# Power.net
KiCad netlist of a schematic drawn in Altium Designer
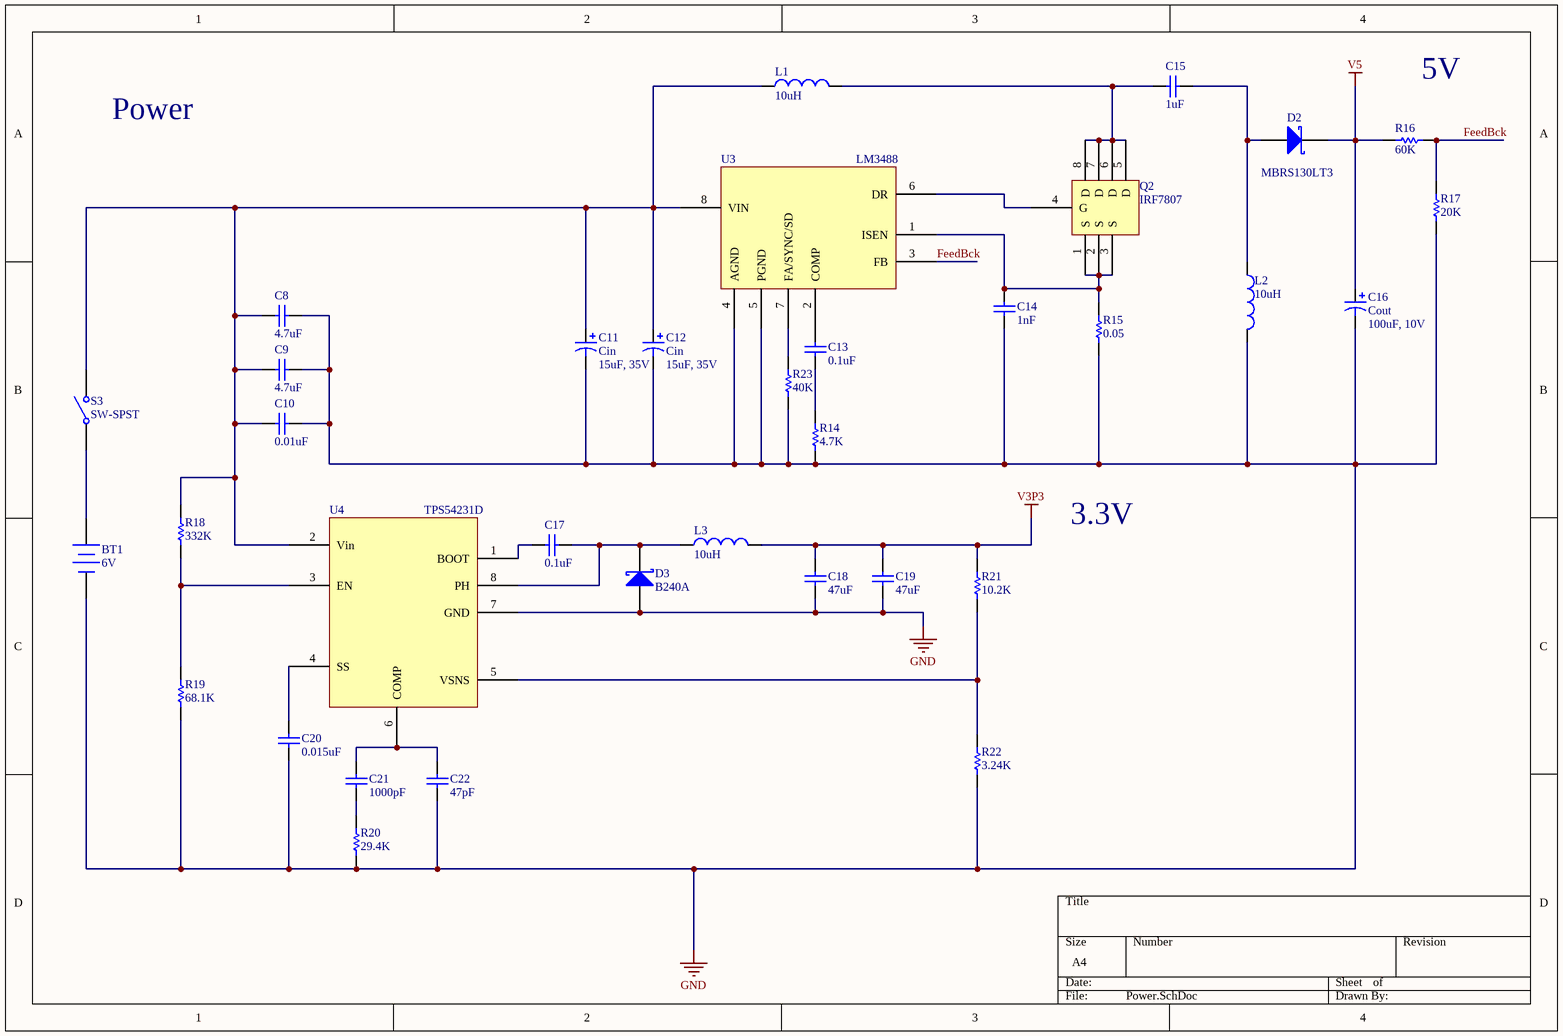
[diagram p0: Power.SchDoc]

(export (version "E")
  (design (tool "Eeschema 10.0.6"))
  (components
    (comp (ref "BT1")
      (value "6V")
      (footprint "BAT-2")
      (description "4xAA")
      (libsource (lib "Miscellaneous Devices") (part "Battery"))
    )
    (comp (ref "C8")
      (value "4.7uF")
      (footprint "own_0603")
      (description "Capacitor")
      (libsource (lib "Miscellaneous Devices") (part "Cap"))
    )
    (comp (ref "C9")
      (value "4.7uF")
      (footprint "own_0603")
      (description "Capacitor")
      (libsource (lib "Miscellaneous Devices") (part "Cap"))
    )
    (comp (ref "C10")
      (value "0.01uF")
      (footprint "own_0603")
      (description "Capacitor")
      (libsource (lib "Miscellaneous Devices") (part "Cap"))
    )
    (comp (ref "C11")
      (value "Cin")
      (footprint "WE-865080542005")
      (description "Polarized Capacitor (Radial)")
      (fields (field (name "ALTIUM_VALUE") "15uF, 35V"))
      (libsource (lib "Miscellaneous Devices") (part "Cap Pol1"))
    )
    (comp (ref "C12")
      (value "Cin")
      (footprint "WE-865080542005")
      (description "Polarized Capacitor (Radial)")
      (fields (field (name "ALTIUM_VALUE") "15uF, 35V"))
      (libsource (lib "Miscellaneous Devices") (part "Cap Pol1"))
    )
    (comp (ref "C13")
      (value "0.1uF")
      (footprint "own_0603")
      (description "Capacitor")
      (libsource (lib "Miscellaneous Devices") (part "Cap"))
    )
    (comp (ref "C14")
      (value "1nF")
      (footprint "own_0603")
      (description "Capacitor")
      (libsource (lib "Miscellaneous Devices") (part "Cap"))
    )
    (comp (ref "C15")
      (value "1uF")
      (footprint "own_0603")
      (description "Capacitor")
      (libsource (lib "Miscellaneous Devices") (part "Cap"))
    )
    (comp (ref "C16")
      (value "Cout")
      (footprint "SMT-HA-V-D")
      (description "Polarized Capacitor (Radial)")
      (fields (field (name "ALTIUM_VALUE") "100uF, 10V"))
      (libsource (lib "Miscellaneous Devices") (part "Cap Pol1"))
    )
    (comp (ref "C17")
      (value "0.1uF")
      (footprint "own_0603")
      (description "Capacitor")
      (libsource (lib "Miscellaneous Devices") (part "Cap"))
    )
    (comp (ref "C18")
      (value "47uF")
      (footprint "own_0603")
      (description "Capacitor")
      (libsource (lib "Miscellaneous Devices") (part "Cap"))
    )
    (comp (ref "C19")
      (value "47uF")
      (footprint "own_0603")
      (description "Capacitor")
      (libsource (lib "Miscellaneous Devices") (part "Cap"))
    )
    (comp (ref "C20")
      (value "0.015uF")
      (footprint "own_0603")
      (description "Capacitor")
      (libsource (lib "Miscellaneous Devices") (part "Cap"))
    )
    (comp (ref "C21")
      (value "1000pF")
      (footprint "own_0603")
      (description "Capacitor")
      (libsource (lib "Miscellaneous Devices") (part "Cap"))
    )
    (comp (ref "C22")
      (value "47pF")
      (footprint "own_0603")
      (description "Capacitor")
      (libsource (lib "Miscellaneous Devices") (part "Cap"))
    )
    (comp (ref "D2")
      (value "MBRS130LT3")
      (footprint "SMB-403A-03-J")
      (description "Schottky Rectifier")
      (libsource (lib "Miscellaneous Devices") (part "Diode 10TQ035"))
    )
    (comp (ref "D3")
      (value "B240A")
      (footprint "SMA-B2XX/A")
      (description "Schottky Rectifier")
      (libsource (lib "Miscellaneous Devices") (part "Diode 10TQ035"))
    )
    (comp (ref "L1")
      (value "10uH")
      (footprint "RLB Series")
      (description "Inductor")
      (libsource (lib "Miscellaneous Devices") (part "Inductor"))
    )
    (comp (ref "L2")
      (value "10uH")
      (footprint "RLB Series")
      (description "Inductor")
      (libsource (lib "Miscellaneous Devices") (part "Inductor"))
    )
    (comp (ref "L3")
      (value "10uH")
      (footprint "RLB Series")
      (description "Inductor")
      (libsource (lib "Miscellaneous Devices") (part "Inductor"))
    )
    (comp (ref "Q2")
      (value "IRF7807")
      (footprint "SO-8")
      (description "MOSFET-8")
      (libsource (lib "Schlib") (part "IRF7807"))
    )
    (comp (ref "R14")
      (value "4.7K")
      (footprint "own_0603")
      (description "Resistor")
      (libsource (lib "Miscellaneous Devices") (part "Res1"))
    )
    (comp (ref "R15")
      (value "0.05")
      (footprint "own_0603")
      (description "Resistor")
      (libsource (lib "Miscellaneous Devices") (part "Res1"))
    )
    (comp (ref "R16")
      (value "60K")
      (footprint "own_0603")
      (description "Resistor")
      (libsource (lib "Miscellaneous Devices") (part "Res1"))
    )
    (comp (ref "R17")
      (value "20K")
      (footprint "own_0603")
      (description "Resistor")
      (libsource (lib "Miscellaneous Devices") (part "Res1"))
    )
    (comp (ref "R18")
      (value "332K")
      (footprint "own_0603")
      (description "Resistor")
      (libsource (lib "Miscellaneous Devices") (part "Res1"))
    )
    (comp (ref "R19")
      (value "68.1K")
      (footprint "own_0603")
      (description "Resistor")
      (libsource (lib "Miscellaneous Devices") (part "Res1"))
    )
    (comp (ref "R20")
      (value "29.4K")
      (footprint "own_0603")
      (description "Resistor")
      (libsource (lib "Miscellaneous Devices") (part "Res1"))
    )
    (comp (ref "R21")
      (value "10.2K")
      (footprint "own_0603")
      (description "Resistor")
      (libsource (lib "Miscellaneous Devices") (part "Res1"))
    )
    (comp (ref "R22")
      (value "3.24K")
      (footprint "own_0603")
      (description "Resistor")
      (libsource (lib "Miscellaneous Devices") (part "Res1"))
    )
    (comp (ref "R23")
      (value "40K")
      (footprint "own_0603")
      (description "Resistor")
      (libsource (lib "Miscellaneous Devices") (part "Res1"))
    )
    (comp (ref "S3")
      (value "SW-SPST")
      (footprint "SPST-2")
      (description "Single-Pole, Single-Throw Switch")
      (libsource (lib "Miscellaneous Devices") (part "SW-SPST"))
    )
    (comp (ref "U3")
      (value "LM3488")
      (footprint "S-PDSO-G8")
      (description "SEPIC 5V")
      (libsource (lib "Schlib") (part "LM3488"))
    )
    (comp (ref "U4")
      (value "TPS54231D")
      (footprint "R-PDSO-G8")
      (description "Buck SD 3.3V")
      (libsource (lib "Schlib") (part "TPS54231D"))
    )
  )
  (nets
    (net (code "1") (name "/FeedBck") (class "Default")
      (node (ref "R16") (pin "1") (pinfunction "1_1") (pintype "passive"))
      (node (ref "R17") (pin "1") (pinfunction "1_1") (pintype "passive"))
      (node (ref "U3") (pin "3") (pinfunction "FB_3") (pintype "passive"))
    )
    (net (code "2") (name "GND") (class "Default")
      (node (ref "BT1") (pin "2") (pinfunction "-_2") (pintype "passive"))
      (node (ref "C10") (pin "2") (pinfunction "2_2") (pintype "passive"))
      (node (ref "C11") (pin "2") (pinfunction "2_2") (pintype "passive"))
      (node (ref "C12") (pin "2") (pinfunction "2_2") (pintype "passive"))
      (node (ref "C14") (pin "1") (pinfunction "1_1") (pintype "passive"))
      (node (ref "C16") (pin "2") (pinfunction "2_2") (pintype "passive"))
      (node (ref "C18") (pin "1") (pinfunction "1_1") (pintype "passive"))
      (node (ref "C19") (pin "1") (pinfunction "1_1") (pintype "passive"))
      (node (ref "C20") (pin "1") (pinfunction "1_1") (pintype "passive"))
      (node (ref "C22") (pin "1") (pinfunction "1_1") (pintype "passive"))
      (node (ref "C8") (pin "2") (pinfunction "2_2") (pintype "passive"))
      (node (ref "C9") (pin "2") (pinfunction "2_2") (pintype "passive"))
      (node (ref "D3") (pin "2") (pinfunction "A_2") (pintype "passive"))
      (node (ref "L2") (pin "2") (pinfunction "2_2") (pintype "passive"))
      (node (ref "R14") (pin "1") (pinfunction "1_1") (pintype "passive"))
      (node (ref "R15") (pin "1") (pinfunction "1_1") (pintype "passive"))
      (node (ref "R17") (pin "2") (pinfunction "2_2") (pintype "passive"))
      (node (ref "R19") (pin "2") (pinfunction "2_2") (pintype "passive"))
      (node (ref "R20") (pin "2") (pinfunction "2_2") (pintype "passive"))
      (node (ref "R22") (pin "2") (pinfunction "2_2") (pintype "passive"))
      (node (ref "R23") (pin "2") (pinfunction "2_2") (pintype "passive"))
      (node (ref "U3") (pin "4") (pinfunction "AGND_4") (pintype "passive"))
      (node (ref "U3") (pin "5") (pinfunction "PGND_5") (pintype "passive"))
      (node (ref "U4") (pin "7") (pinfunction "GND_7") (pintype "passive"))
    )
    (net (code "3") (name "Net-(BT1-+)") (class "Default")
      (node (ref "BT1") (pin "1") (pinfunction "+_1") (pintype "passive"))
      (node (ref "S3") (pin "1") (pinfunction "COMMON_1") (pintype "passive"))
    )
    (net (code "4") (name "Net-(C13-Pad1)") (class "Default")
      (node (ref "C13") (pin "1") (pinfunction "1_1") (pintype "passive"))
      (node (ref "R14") (pin "2") (pinfunction "2_2") (pintype "passive"))
    )
    (net (code "5") (name "Net-(C15-Pad2)") (class "Default")
      (node (ref "C15") (pin "2") (pinfunction "2_2") (pintype "passive"))
      (node (ref "L1") (pin "2") (pinfunction "2_2") (pintype "passive"))
      (node (ref "Q2") (pin "5") (pinfunction "D_5") (pintype "passive"))
      (node (ref "Q2") (pin "6") (pinfunction "D_6") (pintype "passive"))
      (node (ref "Q2") (pin "7") (pinfunction "D_7") (pintype "passive"))
      (node (ref "Q2") (pin "8") (pinfunction "D_8") (pintype "passive"))
    )
    (net (code "6") (name "Net-(C21-Pad1)") (class "Default")
      (node (ref "C21") (pin "1") (pinfunction "1_1") (pintype "passive"))
      (node (ref "R20") (pin "1") (pinfunction "1_1") (pintype "passive"))
    )
    (net (code "7") (name "Net-(D2-A)") (class "Default")
      (node (ref "C15") (pin "1") (pinfunction "1_1") (pintype "passive"))
      (node (ref "D2") (pin "2") (pinfunction "A_2") (pintype "passive"))
      (node (ref "L2") (pin "1") (pinfunction "1_1") (pintype "passive"))
    )
    (net (code "8") (name "Net-(D3-K)") (class "Default")
      (node (ref "C17") (pin "1") (pinfunction "1_1") (pintype "passive"))
      (node (ref "D3") (pin "1") (pinfunction "K_1") (pintype "passive"))
      (node (ref "L3") (pin "1") (pinfunction "1_1") (pintype "passive"))
      (node (ref "U4") (pin "8") (pinfunction "PH_8") (pintype "passive"))
    )
    (net (code "9") (name "Net-(Q2-G)") (class "Default")
      (node (ref "Q2") (pin "4") (pinfunction "G_4") (pintype "passive"))
      (node (ref "U3") (pin "6") (pinfunction "DR_6") (pintype "passive"))
    )
    (net (code "10") (name "Net-(S3-NO)") (class "Default")
      (node (ref "C10") (pin "1") (pinfunction "1_1") (pintype "passive"))
      (node (ref "C11") (pin "1") (pinfunction "1_1") (pintype "passive"))
      (node (ref "C12") (pin "1") (pinfunction "1_1") (pintype "passive"))
      (node (ref "C8") (pin "1") (pinfunction "1_1") (pintype "passive"))
      (node (ref "C9") (pin "1") (pinfunction "1_1") (pintype "passive"))
      (node (ref "L1") (pin "1") (pinfunction "1_1") (pintype "passive"))
      (node (ref "R18") (pin "1") (pinfunction "1_1") (pintype "passive"))
      (node (ref "S3") (pin "2") (pinfunction "NO_2") (pintype "passive"))
      (node (ref "U3") (pin "8") (pinfunction "VIN_8") (pintype "passive"))
      (node (ref "U4") (pin "2") (pinfunction "Vin_2") (pintype "passive"))
    )
    (net (code "11") (name "Net-(U3-COMP)") (class "Default")
      (node (ref "C13") (pin "2") (pinfunction "2_2") (pintype "passive"))
      (node (ref "U3") (pin "2") (pinfunction "COMP_2") (pintype "passive"))
    )
    (net (code "12") (name "Net-(U3-FA{slash}SYNC{slash}SD)") (class "Default")
      (node (ref "R23") (pin "1") (pinfunction "1_1") (pintype "passive"))
      (node (ref "U3") (pin "7") (pinfunction "FA/SYNC/SD_7") (pintype "passive"))
    )
    (net (code "13") (name "Net-(U3-ISEN)") (class "Default")
      (node (ref "C14") (pin "2") (pinfunction "2_2") (pintype "passive"))
      (node (ref "Q2") (pin "1") (pinfunction "S_1") (pintype "passive"))
      (node (ref "Q2") (pin "2") (pinfunction "S_2") (pintype "passive"))
      (node (ref "Q2") (pin "3") (pinfunction "S_3") (pintype "passive"))
      (node (ref "R15") (pin "2") (pinfunction "2_2") (pintype "passive"))
      (node (ref "U3") (pin "1") (pinfunction "ISEN_1") (pintype "passive"))
    )
    (net (code "14") (name "Net-(U4-BOOT)") (class "Default")
      (node (ref "C17") (pin "2") (pinfunction "2_2") (pintype "passive"))
      (node (ref "U4") (pin "1") (pinfunction "BOOT_1") (pintype "passive"))
    )
    (net (code "15") (name "Net-(U4-COMP)") (class "Default")
      (node (ref "C21") (pin "2") (pinfunction "2_2") (pintype "passive"))
      (node (ref "C22") (pin "2") (pinfunction "2_2") (pintype "passive"))
      (node (ref "U4") (pin "6") (pinfunction "COMP_6") (pintype "passive"))
    )
    (net (code "16") (name "Net-(U4-EN)") (class "Default")
      (node (ref "R18") (pin "2") (pinfunction "2_2") (pintype "passive"))
      (node (ref "R19") (pin "1") (pinfunction "1_1") (pintype "passive"))
      (node (ref "U4") (pin "3") (pinfunction "EN_3") (pintype "passive"))
    )
    (net (code "17") (name "Net-(U4-SS)") (class "Default")
      (node (ref "C20") (pin "2") (pinfunction "2_2") (pintype "passive"))
      (node (ref "U4") (pin "4") (pinfunction "SS_4") (pintype "passive"))
    )
    (net (code "18") (name "Net-(U4-VSNS)") (class "Default")
      (node (ref "R21") (pin "2") (pinfunction "2_2") (pintype "passive"))
      (node (ref "R22") (pin "1") (pinfunction "1_1") (pintype "passive"))
      (node (ref "U4") (pin "5") (pinfunction "VSNS_5") (pintype "passive"))
    )
    (net (code "19") (name "V3P3") (class "Default")
      (node (ref "C18") (pin "2") (pinfunction "2_2") (pintype "passive"))
      (node (ref "C19") (pin "2") (pinfunction "2_2") (pintype "passive"))
      (node (ref "L3") (pin "2") (pinfunction "2_2") (pintype "passive"))
      (node (ref "R21") (pin "1") (pinfunction "1_1") (pintype "passive"))
    )
    (net (code "20") (name "V5") (class "Default")
      (node (ref "C16") (pin "1") (pinfunction "1_1") (pintype "passive"))
      (node (ref "D2") (pin "1") (pinfunction "K_1") (pintype "passive"))
      (node (ref "R16") (pin "2") (pinfunction "2_2") (pintype "passive"))
    )
  )
)
